# 01_Power.net
KiCad netlist of a schematic drawn in Altium Designer
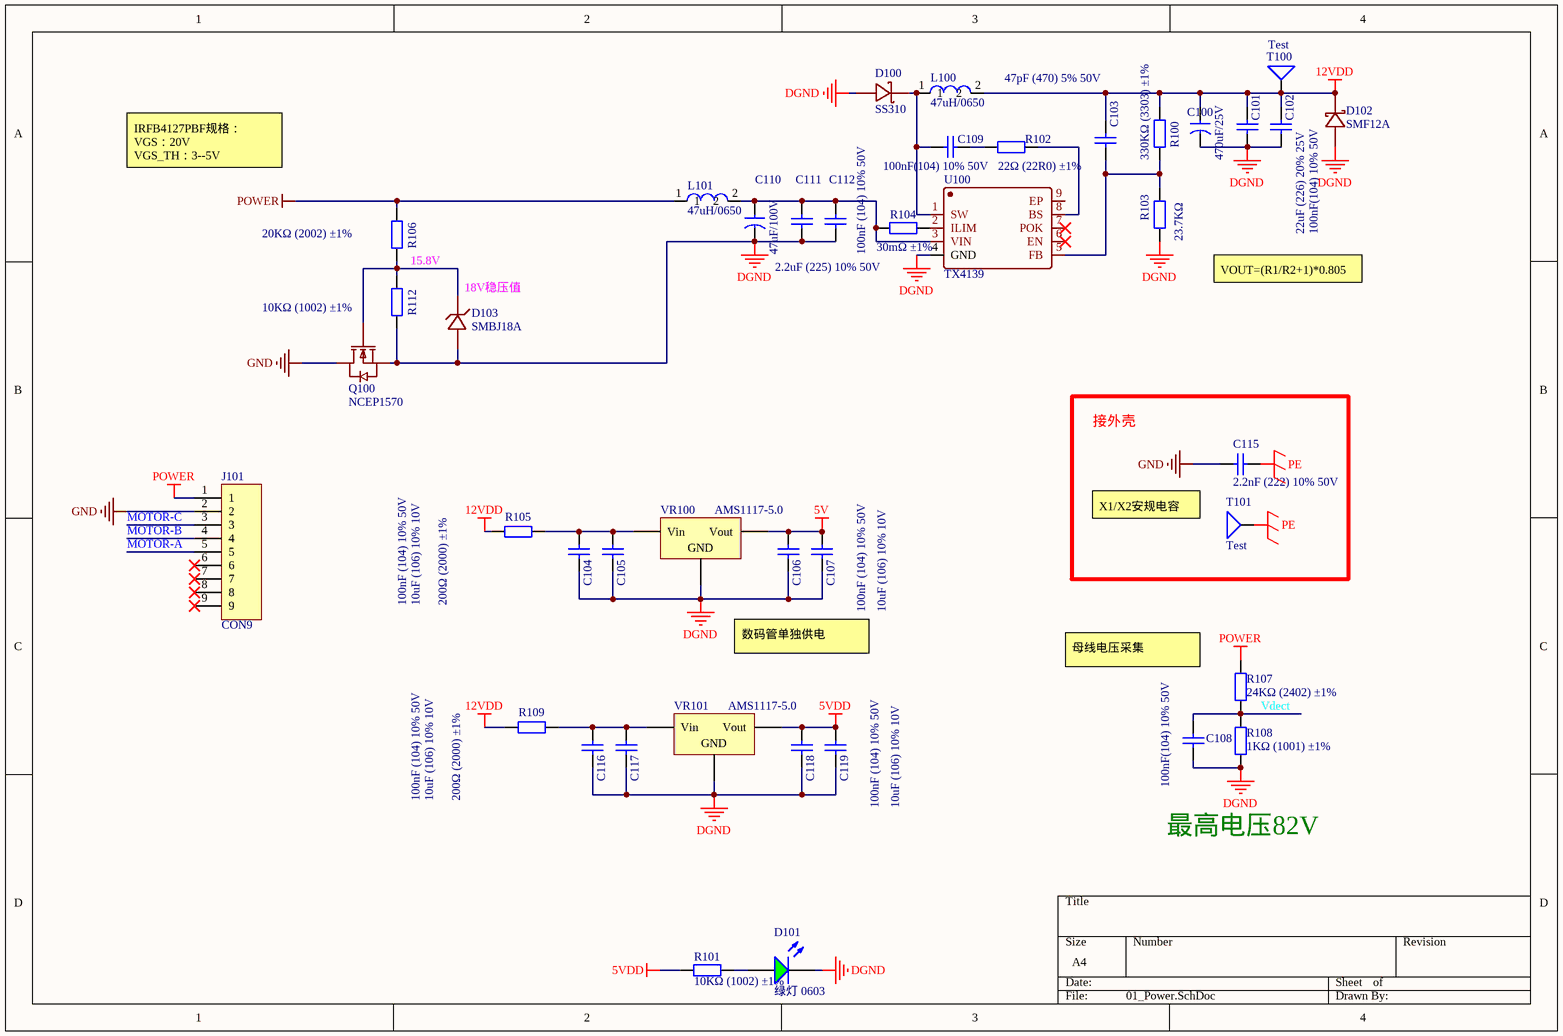
[diagram p0: 01_Power.SchDoc]

(export (version "E")
  (design (tool "Eeschema 10.0.6"))
  (components
    (comp (ref "C100")
      (value "470uF/25V")
      (footprint "47UF/100V")
      (libsource (lib "RayPCB20210502") (part "CapSMT220u_16V"))
    )
    (comp (ref "C101")
      (value "22uF (226) 20% 25V")
      (footprint "0805_C")
      (description "贴片电容")
      (libsource (lib "Miscellaneous Devices LC") (part "0805 22uF (226) 20% 25V"))
    )
    (comp (ref "C102")
      (value "100nF(104) 10% 50V")
      (footprint "0805_C")
      (description "贴片电容")
      (libsource (lib "Miscellaneous Devices LC") (part "0805 100nF(104) 10% 50V"))
    )
    (comp (ref "C103")
      (value "47pF (470) 5% 50V")
      (footprint "0805_C")
      (description "贴片电容")
      (libsource (lib "Miscellaneous Devices LC") (part "0805 47pF (470) 5% 50V"))
    )
    (comp (ref "C104")
      (value "100nF (104) 10% 50V")
      (footprint "0603_C")
      (description "贴片电容")
      (libsource (lib "Miscellaneous Devices LC") (part "0603 100nF (104) 10% 50V"))
    )
    (comp (ref "C105")
      (value "10uF (106) 10% 10V")
      (footprint "0603_C")
      (description "贴片电容")
      (libsource (lib "Miscellaneous Devices LC") (part "0603 10uF (106) 10% 10V"))
    )
    (comp (ref "C106")
      (value "100nF (104) 10% 50V")
      (footprint "0603_C")
      (description "贴片电容")
      (libsource (lib "Miscellaneous Devices LC") (part "0603 100nF (104) 10% 50V"))
    )
    (comp (ref "C107")
      (value "10uF (106) 10% 10V")
      (footprint "0603_C")
      (description "贴片电容")
      (libsource (lib "Miscellaneous Devices LC") (part "0603 10uF (106) 10% 10V"))
    )
    (comp (ref "C108")
      (value "100nF(104) 10% 50V")
      (footprint "0805_C")
      (description "贴片电容")
      (libsource (lib "Miscellaneous Devices LC") (part "0805 100nF(104) 10% 50V"))
    )
    (comp (ref "C109")
      (value "100nF(104) 10% 50V")
      (footprint "0805_C")
      (description "贴片电容")
      (libsource (lib "Miscellaneous Devices LC") (part "0805 100nF(104) 10% 50V"))
    )
    (comp (ref "C110")
      (value "47uF/100V")
      (footprint "47UF/100V")
      (libsource (lib "RayPCB20210502") (part "CapSMT220u_16V"))
    )
    (comp (ref "C111")
      (value "2.2uF (225) 10% 50V")
      (footprint "1206_C")
      (description "贴片电容")
      (libsource (lib "Miscellaneous Devices LC") (part "1206 2.2uF (225) 10% 50V"))
    )
    (comp (ref "C112")
      (value "100nF (104) 10% 50V")
      (footprint "1206_C")
      (description "贴片电容")
      (libsource (lib "Miscellaneous Devices LC") (part "1206 100nF (104) 10% 50V"))
    )
    (comp (ref "C115")
      (value "2.2nF (222) 10% 50V")
      (footprint "X1/Y1 500V")
      (description "贴片电容")
      (libsource (lib "Miscellaneous Devices LC") (part "0603 2.2nF (222) 10% 50V"))
    )
    (comp (ref "C116")
      (value "100nF (104) 10% 50V")
      (footprint "0603_C")
      (description "贴片电容")
      (libsource (lib "Miscellaneous Devices LC") (part "0603 100nF (104) 10% 50V"))
    )
    (comp (ref "C117")
      (value "10uF (106) 10% 10V")
      (footprint "0603_C")
      (description "贴片电容")
      (libsource (lib "Miscellaneous Devices LC") (part "0603 10uF (106) 10% 10V"))
    )
    (comp (ref "C118")
      (value "100nF (104) 10% 50V")
      (footprint "0603_C")
      (description "贴片电容")
      (libsource (lib "Miscellaneous Devices LC") (part "0603 100nF (104) 10% 50V"))
    )
    (comp (ref "C119")
      (value "10uF (106) 10% 10V")
      (footprint "0603_C")
      (description "贴片电容")
      (libsource (lib "Miscellaneous Devices LC") (part "0603 10uF (106) 10% 10V"))
    )
    (comp (ref "D100") (value "SS310") (footprint "SS310") (libsource (lib "Schlibv2") (part "SS310")))
    (comp (ref "D101")
      (value "绿灯 0603")
      (footprint "0603_LED_S1")
      (description "发光二极管")
      (libsource (lib "Miscellaneous Devices LC") (part "0603 绿灯"))
    )
    (comp (ref "D102")
      (value "SMF12A")
      (footprint "SMF12A - duplicate")
      (libsource (lib "RayPCB20210502") (part "SMF12A"))
    )
    (comp (ref "D103") (value "SMBJ18A") (footprint "SMBJ18A") (libsource (lib "Schlibv2") (part "1N4746A")))
    (comp (ref "J101")
      (value "CON9")
      (footprint "CON9 9.5mm")
      (libsource (lib "RayPCB20210502") (part "CON9"))
    )
    (comp (ref "L100")
      (value "47uH/0650")
      (footprint "0650_47uH")
      (libsource (lib "RayPCB20210502") (part "Inductor"))
    )
    (comp (ref "L101")
      (value "47uH/0650")
      (footprint "0650_47uH")
      (libsource (lib "RayPCB20210502") (part "Inductor"))
    )
    (comp (ref "Q100")
      (value "NCEP1570")
      (footprint "IRFB4127")
      (libsource (lib "RayPCB20210502") (part "IRFB4127PBF"))
    )
    (comp (ref "R100")
      (value "330KΩ (3303) ±1%")
      (footprint "0805_R")
      (description "贴片电阻")
      (libsource (lib "Miscellaneous Devices LC") (part "0805 330KΩ (3303) 1%"))
    )
    (comp (ref "R101")
      (value "10KΩ (1002) ±1%")
      (footprint "0603_R")
      (description "贴片电阻")
      (libsource (lib "Miscellaneous Devices LC") (part "0603 10KΩ (1002) 1%"))
    )
    (comp (ref "R102")
      (value "22Ω (22R0) ±1%")
      (footprint "0805_R")
      (description "贴片电阻")
      (libsource (lib "Miscellaneous Devices LC") (part "0805 22Ω (22R0) 1%"))
    )
    (comp (ref "R103")
      (value "23.7KΩ")
      (footprint "0805_R")
      (description "贴片电阻")
      (libsource (lib "") (part "0805 22Ω (22R0) 1%_1"))
    )
    (comp (ref "R104")
      (value "30mΩ ±1%")
      (footprint "0603_R")
      (description "贴片电阻")
      (libsource (lib "Miscellaneous Devices LC") (part "0603 100KΩ (1003) 1%"))
    )
    (comp (ref "R105")
      (value "200Ω (2000) ±1%")
      (footprint "1206_R")
      (description "贴片电阻")
      (libsource (lib "Miscellaneous Devices LC") (part "1206 300Ω (3000) 1%"))
    )
    (comp (ref "R106")
      (value "20KΩ (2002) ±1%")
      (footprint "0805_R")
      (description "贴片电阻")
      (libsource (lib "Miscellaneous Devices LC") (part "0805 20KΩ (2002) 1%"))
    )
    (comp (ref "R107")
      (value "24KΩ (2402) ±1%")
      (footprint "1206_R")
      (description "贴片电阻")
      (libsource (lib "Miscellaneous Devices LC") (part "1206 0Ω (0R0) 1%"))
    )
    (comp (ref "R108")
      (value "1KΩ (1001) ±1%")
      (footprint "0805_R")
      (description "贴片电阻")
      (libsource (lib "Miscellaneous Devices LC") (part "0805 1KΩ (1001) 1%"))
    )
    (comp (ref "R109")
      (value "200Ω (2000) ±1%")
      (footprint "1206_R")
      (description "贴片电阻")
      (libsource (lib "Miscellaneous Devices LC") (part "1206 300Ω (3000) 1%"))
    )
    (comp (ref "R112")
      (value "10KΩ (1002) ±1%")
      (footprint "0805_R")
      (description "贴片电阻")
      (libsource (lib "Miscellaneous Devices LC") (part "0805 10KΩ (1002) 1%"))
    )
    (comp (ref "T100")
      (value "Test")
      (footprint "Testpoint")
      (libsource (lib "RayPCB20210502") (part "TestPad"))
    )
    (comp (ref "T101") (value "Test") (footprint "接地螺丝孔") (libsource (lib "RayPCB20210502") (part "TestPad")))
    (comp (ref "U100")
      (value "TX4139")
      (footprint "ESOP8")
      (libsource (lib "RayPCB20210502") (part "TX4139"))
    )
    (comp (ref "VR100")
      (value "AMS1117-5.0")
      (footprint "SOT-223")
      (description "低压差线性稳压(LDO)")
      (libsource (lib "Miscellaneous Devices LC") (part "SOT-223 AMS1117-5.0"))
    )
    (comp (ref "VR101")
      (value "AMS1117-5.0")
      (footprint "SOT-223")
      (description "低压差线性稳压(LDO)")
      (libsource (lib "Miscellaneous Devices LC") (part "SOT-223 AMS1117-5.0"))
    )
  )
  (nets
    (net (code "1") (name "/MOTOR-A") (class "Default")
      (node (ref "J101") (pin "5") (pinfunction "5_5") (pintype "passive"))
    )
    (net (code "2") (name "/MOTOR-B") (class "Default")
      (node (ref "J101") (pin "4") (pinfunction "4_4") (pintype "passive"))
    )
    (net (code "3") (name "/MOTOR-C") (class "Default")
      (node (ref "J101") (pin "3") (pinfunction "3_3") (pintype "passive"))
    )
    (net (code "4") (name "/Vdect") (class "Default")
      (node (ref "C108") (pin "2") (pinfunction "2_2") (pintype "passive"))
      (node (ref "R107") (pin "1") (pinfunction "1_1") (pintype "passive"))
      (node (ref "R108") (pin "2") (pinfunction "2_2") (pintype "passive"))
    )
    (net (code "5") (name "5V") (class "Default")
      (node (ref "C106") (pin "2") (pinfunction "2_2") (pintype "passive"))
      (node (ref "C107") (pin "2") (pinfunction "2_2") (pintype "passive"))
      (node (ref "VR100") (pin "2") (pinfunction "Vout_2") (pintype "passive"))
    )
    (net (code "6") (name "5VDD") (class "Default")
      (node (ref "C118") (pin "2") (pinfunction "2_2") (pintype "passive"))
      (node (ref "C119") (pin "2") (pinfunction "2_2") (pintype "passive"))
      (node (ref "R101") (pin "2") (pinfunction "2_2") (pintype "passive"))
      (node (ref "VR101") (pin "2") (pinfunction "Vout_2") (pintype "passive"))
    )
    (net (code "7") (name "12VDD") (class "Default")
      (node (ref "C100") (pin "1") (pintype "passive"))
      (node (ref "C101") (pin "2") (pinfunction "2_2") (pintype "passive"))
      (node (ref "C102") (pin "2") (pinfunction "2_2") (pintype "passive"))
      (node (ref "C103") (pin "2") (pinfunction "2_2") (pintype "passive"))
      (node (ref "D102") (pin "1") (pinfunction "K_1") (pintype "passive"))
      (node (ref "L100") (pin "2") (pinfunction "2_2") (pintype "passive"))
      (node (ref "R100") (pin "2") (pinfunction "2_2") (pintype "passive"))
      (node (ref "R105") (pin "1") (pinfunction "1_1") (pintype "passive"))
      (node (ref "R109") (pin "1") (pinfunction "1_1") (pintype "passive"))
      (node (ref "T100") (pin "1") (pinfunction "1_1") (pintype "passive"))
    )
    (net (code "8") (name "DGND") (class "Default")
      (node (ref "C100") (pin "2") (pintype "passive"))
      (node (ref "C101") (pin "1") (pinfunction "1_1") (pintype "passive"))
      (node (ref "C102") (pin "1") (pinfunction "1_1") (pintype "passive"))
      (node (ref "C104") (pin "1") (pinfunction "1_1") (pintype "passive"))
      (node (ref "C105") (pin "1") (pinfunction "1_1") (pintype "passive"))
      (node (ref "C106") (pin "1") (pinfunction "1_1") (pintype "passive"))
      (node (ref "C107") (pin "1") (pinfunction "1_1") (pintype "passive"))
      (node (ref "C108") (pin "1") (pinfunction "1_1") (pintype "passive"))
      (node (ref "C110") (pin "2") (pintype "passive"))
      (node (ref "C111") (pin "1") (pinfunction "1_1") (pintype "passive"))
      (node (ref "C112") (pin "1") (pinfunction "1_1") (pintype "passive"))
      (node (ref "C116") (pin "1") (pinfunction "1_1") (pintype "passive"))
      (node (ref "C117") (pin "1") (pinfunction "1_1") (pintype "passive"))
      (node (ref "C118") (pin "1") (pinfunction "1_1") (pintype "passive"))
      (node (ref "C119") (pin "1") (pinfunction "1_1") (pintype "passive"))
      (node (ref "D100") (pin "2") (pinfunction "A_2") (pintype "passive"))
      (node (ref "D101") (pin "K") (pinfunction "K_K") (pintype "passive"))
      (node (ref "D102") (pin "2") (pinfunction "A_2") (pintype "passive"))
      (node (ref "D103") (pin "1") (pinfunction "A_1") (pintype "passive"))
      (node (ref "Q100") (pin "3") (pinfunction "S_3") (pintype "passive"))
      (node (ref "R103") (pin "1") (pinfunction "1_1") (pintype "passive"))
      (node (ref "R108") (pin "1") (pinfunction "1_1") (pintype "passive"))
      (node (ref "R112") (pin "1") (pinfunction "1_1") (pintype "passive"))
      (node (ref "U100") (pin "4") (pinfunction "GND_4") (pintype "passive"))
      (node (ref "VR100") (pin "1") (pinfunction "GND_1") (pintype "passive"))
      (node (ref "VR101") (pin "1") (pinfunction "GND_1") (pintype "passive"))
    )
    (net (code "9") (name "GND") (class "Default")
      (node (ref "C115") (pin "1") (pinfunction "1_1") (pintype "passive"))
      (node (ref "J101") (pin "2") (pinfunction "2_2") (pintype "passive"))
      (node (ref "Q100") (pin "2") (pinfunction "D_2") (pintype "passive"))
    )
    (net (code "10") (name "Net-(C109-Pad2)") (class "Default")
      (node (ref "C109") (pin "2") (pinfunction "2_2") (pintype "passive"))
      (node (ref "R102") (pin "1") (pinfunction "1_1") (pintype "passive"))
    )
    (net (code "11") (name "Net-(D100-K)") (class "Default")
      (node (ref "C109") (pin "1") (pinfunction "1_1") (pintype "passive"))
      (node (ref "D100") (pin "1") (pinfunction "K_1") (pintype "passive"))
      (node (ref "L100") (pin "1") (pinfunction "1_1") (pintype "passive"))
      (node (ref "U100") (pin "1") (pinfunction "SW_1") (pintype "passive"))
    )
    (net (code "12") (name "Net-(D101-PadA)") (class "Default")
      (node (ref "D101") (pin "A") (pinfunction "A_A") (pintype "passive"))
      (node (ref "R101") (pin "1") (pinfunction "1_1") (pintype "passive"))
    )
    (net (code "13") (name "Net-(D103-K)") (class "Default")
      (node (ref "D103") (pin "2") (pinfunction "K_2") (pintype "passive"))
      (node (ref "Q100") (pin "1") (pinfunction "G_1") (pintype "passive"))
      (node (ref "R106") (pin "1") (pinfunction "1_1") (pintype "passive"))
      (node (ref "R112") (pin "2") (pinfunction "2_2") (pintype "passive"))
    )
    (net (code "14") (name "Net-(U100-BS)") (class "Default")
      (node (ref "R102") (pin "2") (pinfunction "2_2") (pintype "passive"))
      (node (ref "U100") (pin "8") (pinfunction "BS_8") (pintype "passive"))
    )
    (net (code "15") (name "Net-(U100-FB)") (class "Default")
      (node (ref "C103") (pin "1") (pinfunction "1_1") (pintype "passive"))
      (node (ref "R100") (pin "1") (pinfunction "1_1") (pintype "passive"))
      (node (ref "R103") (pin "2") (pinfunction "2_2") (pintype "passive"))
      (node (ref "U100") (pin "5") (pinfunction "FB_5") (pintype "passive"))
    )
    (net (code "16") (name "Net-(U100-ILIM)") (class "Default")
      (node (ref "R104") (pin "1") (pinfunction "1_1") (pintype "passive"))
      (node (ref "U100") (pin "2") (pinfunction "ILIM_2") (pintype "passive"))
    )
    (net (code "17") (name "Net-(U100-VIN)") (class "Default")
      (node (ref "C110") (pin "1") (pintype "passive"))
      (node (ref "C111") (pin "2") (pinfunction "2_2") (pintype "passive"))
      (node (ref "C112") (pin "2") (pinfunction "2_2") (pintype "passive"))
      (node (ref "L101") (pin "2") (pinfunction "2_2") (pintype "passive"))
      (node (ref "R104") (pin "2") (pinfunction "2_2") (pintype "passive"))
      (node (ref "U100") (pin "3") (pinfunction "VIN_3") (pintype "passive"))
    )
    (net (code "18") (name "Net-(VR100-Vin)") (class "Default")
      (node (ref "C104") (pin "2") (pinfunction "2_2") (pintype "passive"))
      (node (ref "C105") (pin "2") (pinfunction "2_2") (pintype "passive"))
      (node (ref "R105") (pin "2") (pinfunction "2_2") (pintype "passive"))
      (node (ref "VR100") (pin "3") (pinfunction "Vin_3") (pintype "passive"))
    )
    (net (code "19") (name "Net-(VR101-Vin)") (class "Default")
      (node (ref "C116") (pin "2") (pinfunction "2_2") (pintype "passive"))
      (node (ref "C117") (pin "2") (pinfunction "2_2") (pintype "passive"))
      (node (ref "R109") (pin "2") (pinfunction "2_2") (pintype "passive"))
      (node (ref "VR101") (pin "3") (pinfunction "Vin_3") (pintype "passive"))
    )
    (net (code "20") (name "PE") (class "Default")
      (node (ref "C115") (pin "2") (pinfunction "2_2") (pintype "passive"))
      (node (ref "T101") (pin "1") (pinfunction "1_1") (pintype "passive"))
    )
    (net (code "21") (name "POWER") (class "Default")
      (node (ref "J101") (pin "1") (pinfunction "1_1") (pintype "passive"))
      (node (ref "L101") (pin "1") (pinfunction "1_1") (pintype "passive"))
      (node (ref "R106") (pin "2") (pinfunction "2_2") (pintype "passive"))
      (node (ref "R107") (pin "2") (pinfunction "2_2") (pintype "passive"))
    )
    (net (code "22") (name "unconnected-(J101-Pad6)") (class "Default")
      (node (ref "J101") (pin "6") (pinfunction "6_6") (pintype "passive+no_connect"))
    )
    (net (code "23") (name "unconnected-(J101-Pad7)") (class "Default")
      (node (ref "J101") (pin "7") (pinfunction "7_7") (pintype "passive+no_connect"))
    )
    (net (code "24") (name "unconnected-(J101-Pad8)") (class "Default")
      (node (ref "J101") (pin "8") (pinfunction "8_8") (pintype "passive+no_connect"))
    )
    (net (code "25") (name "unconnected-(J101-Pad9)") (class "Default")
      (node (ref "J101") (pin "9") (pinfunction "9_9") (pintype "passive+no_connect"))
    )
    (net (code "26") (name "unconnected-(U100-EN-Pad6)") (class "Default")
      (node (ref "U100") (pin "6") (pinfunction "EN_6") (pintype "passive+no_connect"))
    )
    (net (code "27") (name "unconnected-(U100-EP-Pad9)") (class "Default")
      (node (ref "U100") (pin "9") (pinfunction "EP_9") (pintype "passive"))
    )
    (net (code "28") (name "unconnected-(U100-POK-Pad7)") (class "Default")
      (node (ref "U100") (pin "7") (pinfunction "POK_7") (pintype "passive+no_connect"))
    )
  )
)
